# V2.net
KiCad netlist of a schematic drawn in Altium Designer
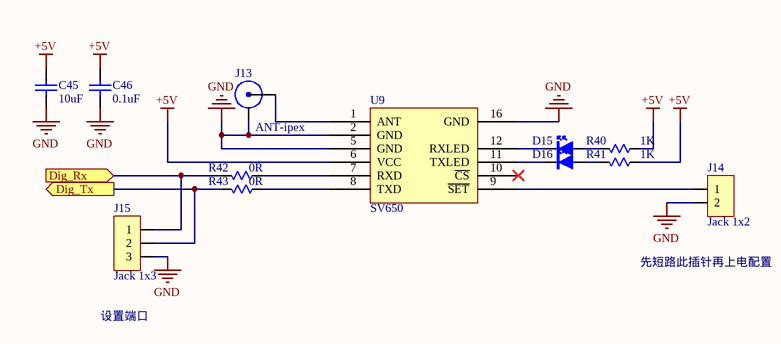
[diagram p0: 海关全向控制器主控板电路V2_数传电路.SchDoc]

(export (version "E")
  (design (tool "Eeschema 10.0.6"))
  (components
    (comp (ref "C45") (value "10uF") (footprint "C0603") (libsource (lib "SMD") (part "Cap Semi")))
    (comp (ref "C46") (value "0.1uF") (footprint "C0603") (libsource (lib "SMD") (part "Cap Semi")))
    (comp (ref "D15")
      (value "LED")
      (footprint "LED0603")
      (libsource (lib "Passive Components Class") (part "LED"))
    )
    (comp (ref "D16")
      (value "LED")
      (footprint "LED0603")
      (libsource (lib "Passive Components Class") (part "LED"))
    )
    (comp (ref "J13") (value "ANT-ipex") (footprint "IPEX") (libsource (lib "RLCYDF") (part "ANT-ipex")))
    (comp (ref "J14")
      (value "Jack 1x2")
      (footprint "HY-2A")
      (description "插座")
      (libsource (lib "Connector") (part "Jack 1x2"))
    )
    (comp (ref "J15")
      (value "Jack 1x3")
      (footprint "35363-0360")
      (description "插座")
      (libsource (lib "Connector") (part "Jack 1x3"))
    )
    (comp (ref "R40")
      (value "1K")
      (footprint "R0603")
      (description "Resistor")
      (fields (field (name "PUBLISHER") "Altium Limited"))
      (libsource (lib "UP-Robot") (part "Res"))
    )
    (comp (ref "R41")
      (value "1K")
      (footprint "R0603")
      (description "Resistor")
      (fields (field (name "PUBLISHER") "Altium Limited"))
      (libsource (lib "UP-Robot") (part "Res"))
    )
    (comp (ref "R42")
      (value "0R")
      (footprint "R0603")
      (description "Resistor")
      (fields (field (name "PUBLISHER") "Altium Limited"))
      (libsource (lib "UP-Robot") (part "Res"))
    )
    (comp (ref "R43")
      (value "0R")
      (footprint "R0603")
      (description "Resistor")
      (fields (field (name "PUBLISHER") "Altium Limited"))
      (libsource (lib "UP-Robot") (part "Res"))
    )
    (comp (ref "U9") (value "SV650") (footprint "SV650") (libsource (lib "Module") (part "SV650")))
  )
  (nets
    (net (code "1") (name "+5V") (class "Default")
      (node (ref "C45") (pin "2") (pinfunction "2_2") (pintype "passive"))
      (node (ref "C46") (pin "2") (pinfunction "2_2") (pintype "passive"))
      (node (ref "R40") (pin "1") (pinfunction "1_1") (pintype "passive"))
      (node (ref "R41") (pin "1") (pinfunction "1_1") (pintype "passive"))
      (node (ref "U9") (pin "6") (pinfunction "VCC_6") (pintype "passive"))
    )
    (net (code "2") (name "/Dig_Rx") (class "Default")
      (node (ref "J15") (pin "1") (pinfunction "1_1") (pintype "passive"))
      (node (ref "R42") (pin "2") (pinfunction "2_2") (pintype "passive"))
    )
    (net (code "3") (name "/Dig_Tx") (class "Default")
      (node (ref "J15") (pin "2") (pinfunction "2_2") (pintype "passive"))
      (node (ref "R43") (pin "2") (pinfunction "2_2") (pintype "passive"))
    )
    (net (code "4") (name "GND") (class "Default")
      (node (ref "C45") (pin "1") (pinfunction "1_1") (pintype "passive"))
      (node (ref "C46") (pin "1") (pinfunction "1_1") (pintype "passive"))
      (node (ref "J13") (pin "2") (pinfunction "GND_2") (pintype "passive"))
      (node (ref "J14") (pin "2") (pinfunction "2_2") (pintype "passive"))
      (node (ref "J15") (pin "3") (pinfunction "3_3") (pintype "passive"))
      (node (ref "U9") (pin "16") (pinfunction "GND_16") (pintype "passive"))
      (node (ref "U9") (pin "2") (pinfunction "GND_2") (pintype "passive"))
      (node (ref "U9") (pin "5") (pinfunction "GND_5") (pintype "passive"))
    )
    (net (code "5") (name "Net-(D15-A)") (class "Default")
      (node (ref "D15") (pin "1") (pinfunction "A_1") (pintype "passive"))
      (node (ref "R40") (pin "2") (pinfunction "2_2") (pintype "passive"))
    )
    (net (code "6") (name "Net-(D15-K)") (class "Default")
      (node (ref "D15") (pin "2") (pinfunction "K_2") (pintype "passive"))
      (node (ref "U9") (pin "12") (pinfunction "RXLED_12") (pintype "passive"))
    )
    (net (code "7") (name "Net-(D16-A)") (class "Default")
      (node (ref "D16") (pin "1") (pinfunction "A_1") (pintype "passive"))
      (node (ref "R41") (pin "2") (pinfunction "2_2") (pintype "passive"))
    )
    (net (code "8") (name "Net-(D16-K)") (class "Default")
      (node (ref "D16") (pin "2") (pinfunction "K_2") (pintype "passive"))
      (node (ref "U9") (pin "11") (pinfunction "TXLED_11") (pintype "passive"))
    )
    (net (code "9") (name "Net-(J13-ANT)") (class "Default")
      (node (ref "J13") (pin "1") (pinfunction "ANT_1") (pintype "passive"))
      (node (ref "U9") (pin "1") (pinfunction "ANT_1") (pintype "passive"))
    )
    (net (code "10") (name "Net-(U9-RXD)") (class "Default")
      (node (ref "R42") (pin "1") (pinfunction "1_1") (pintype "passive"))
      (node (ref "U9") (pin "7") (pinfunction "RXD_7") (pintype "passive"))
    )
    (net (code "11") (name "Net-(U9-TXD)") (class "Default")
      (node (ref "R43") (pin "1") (pinfunction "1_1") (pintype "passive"))
      (node (ref "U9") (pin "8") (pinfunction "TXD_8") (pintype "passive"))
    )
    (net (code "12") (name "Net-(U9-~{SET})") (class "Default")
      (node (ref "J14") (pin "1") (pinfunction "1_1") (pintype "passive"))
      (node (ref "U9") (pin "9") (pinfunction "~{SET}_9") (pintype "passive"))
    )
    (net (code "13") (name "unconnected-(U9-~{CS}-Pad10)") (class "Default")
      (node (ref "U9") (pin "10") (pinfunction "~{CS}_10") (pintype "passive+no_connect"))
    )
  )
)
